# 03_-_OV2640.net
KiCad netlist of a schematic drawn in Altium Designer
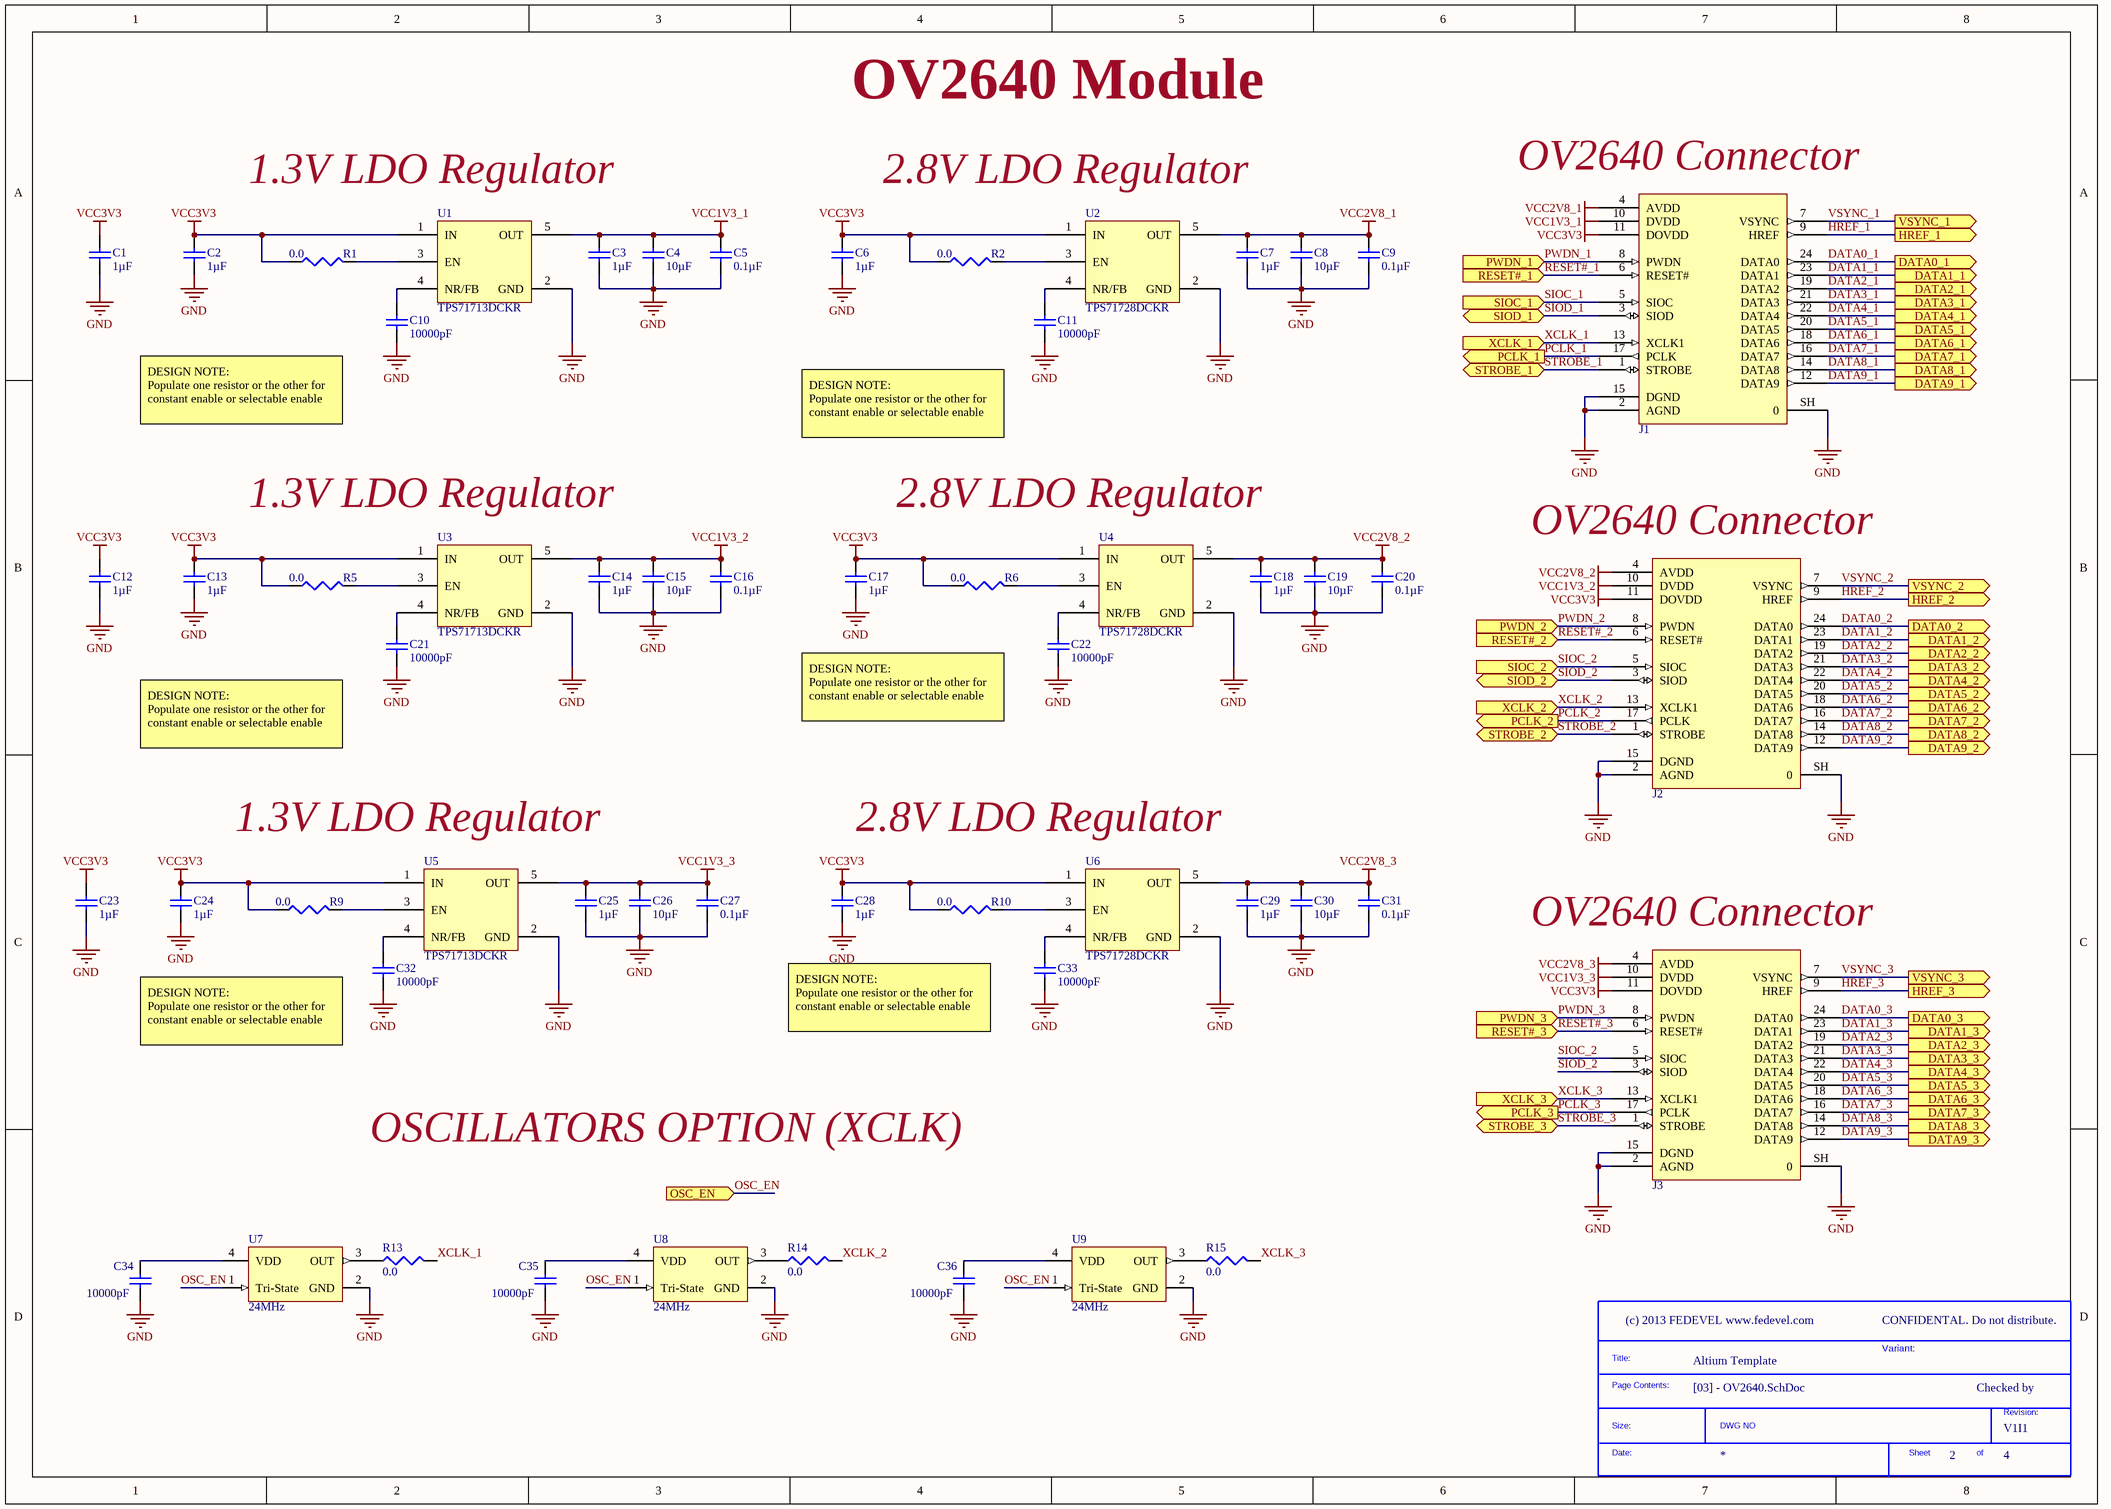
[diagram p0: [03] - OV2640.SchDoc]

(export (version "E")
  (design (tool "Eeschema 10.0.6"))
  (components
    (comp (ref "C1")
      (value "GRM188R71C105KA12D")
      (footprint "CAP-0603")
      (description "CAP CER 1UF 16V X7R 0603")
      (fields
        (field (name "MANUFACTURER") "Murata Electronics North America")
        (field (name "TOLERANCE") "±10%")
        (field (name "CAPACITANCE") "1µF")
      )
      (libsource (lib "camera_module") (part "GRM188R71C105KA12D"))
    )
    (comp (ref "C2")
      (value "GRM188R71C105KA12D")
      (footprint "CAP-0603")
      (description "CAP CER 1UF 16V X7R 0603")
      (fields
        (field (name "MANUFACTURER") "Murata Electronics North America")
        (field (name "TOLERANCE") "±10%")
        (field (name "CAPACITANCE") "1µF")
      )
      (libsource (lib "camera_module") (part "GRM188R71C105KA12D"))
    )
    (comp (ref "C3")
      (value "GRM188R71C105KA12D")
      (footprint "CAP-0603")
      (description "CAP CER 1UF 16V X7R 0603")
      (fields
        (field (name "MANUFACTURER") "Murata Electronics North America")
        (field (name "TOLERANCE") "±10%")
        (field (name "CAPACITANCE") "1µF")
      )
      (libsource (lib "camera_module") (part "GRM188R71C105KA12D"))
    )
    (comp (ref "C4")
      (value "GRM21BR61E106KA73L")
      (footprint "CAP-0805")
      (description "CAP CER 10UF 25V X5R 0805")
      (fields
        (field (name "MANUFACTURER") "Murata Electronics North America")
        (field (name "TOLERANCE") "±10%")
        (field (name "CAPACITANCE") "10µF")
      )
      (libsource (lib "camera_module") (part "GRM21BR61E106KA73L"))
    )
    (comp (ref "C5")
      (value "GRM188R71C104KA01D")
      (footprint "CAP-0603")
      (description "CAP CER 0.1UF 16V X7R 0603")
      (fields
        (field (name "MANUFACTURER") "Murata Electronics North America")
        (field (name "TOLERANCE") "±10%")
        (field (name "CAPACITANCE") "0.1µF")
      )
      (libsource (lib "camera_module") (part "GRM188R71C104KA01D"))
    )
    (comp (ref "C6")
      (value "GRM188R71C105KA12D")
      (footprint "CAP-0603")
      (description "CAP CER 1UF 16V X7R 0603")
      (fields
        (field (name "MANUFACTURER") "Murata Electronics North America")
        (field (name "TOLERANCE") "±10%")
        (field (name "CAPACITANCE") "1µF")
      )
      (libsource (lib "camera_module") (part "GRM188R71C105KA12D"))
    )
    (comp (ref "C7")
      (value "GRM188R71C105KA12D")
      (footprint "CAP-0603")
      (description "CAP CER 1UF 16V X7R 0603")
      (fields
        (field (name "MANUFACTURER") "Murata Electronics North America")
        (field (name "TOLERANCE") "±10%")
        (field (name "CAPACITANCE") "1µF")
      )
      (libsource (lib "camera_module") (part "GRM188R71C105KA12D"))
    )
    (comp (ref "C8")
      (value "GRM21BR61E106KA73L")
      (footprint "CAP-0805")
      (description "CAP CER 10UF 25V X5R 0805")
      (fields
        (field (name "MANUFACTURER") "Murata Electronics North America")
        (field (name "TOLERANCE") "±10%")
        (field (name "CAPACITANCE") "10µF")
      )
      (libsource (lib "camera_module") (part "GRM21BR61E106KA73L"))
    )
    (comp (ref "C9")
      (value "GRM188R71C104KA01D")
      (footprint "CAP-0603")
      (description "CAP CER 0.1UF 16V X7R 0603")
      (fields
        (field (name "MANUFACTURER") "Murata Electronics North America")
        (field (name "TOLERANCE") "±10%")
        (field (name "CAPACITANCE") "0.1µF")
      )
      (libsource (lib "camera_module") (part "GRM188R71C104KA01D"))
    )
    (comp (ref "C10")
      (value "GRM188R71E103KA01D")
      (footprint "CAP-0603")
      (description "CAP CER 10000PF 25V X7R 0603")
      (fields
        (field (name "MANUFACTURER") "Murata Electronics North America")
        (field (name "TOLERANCE") "±10%")
        (field (name "CAPACITANCE") "10000pF")
      )
      (libsource (lib "camera_module") (part "GRM188R71E103KA01D"))
    )
    (comp (ref "C11")
      (value "GRM188R71E103KA01D")
      (footprint "CAP-0603")
      (description "CAP CER 10000PF 25V X7R 0603")
      (fields
        (field (name "MANUFACTURER") "Murata Electronics North America")
        (field (name "TOLERANCE") "±10%")
        (field (name "CAPACITANCE") "10000pF")
      )
      (libsource (lib "camera_module") (part "GRM188R71E103KA01D"))
    )
    (comp (ref "C12")
      (value "GRM188R71C105KA12D")
      (footprint "CAP-0603")
      (description "CAP CER 1UF 16V X7R 0603")
      (fields
        (field (name "MANUFACTURER") "Murata Electronics North America")
        (field (name "TOLERANCE") "±10%")
        (field (name "CAPACITANCE") "1µF")
      )
      (libsource (lib "camera_module") (part "GRM188R71C105KA12D"))
    )
    (comp (ref "C13")
      (value "GRM188R71C105KA12D")
      (footprint "CAP-0603")
      (description "CAP CER 1UF 16V X7R 0603")
      (fields
        (field (name "MANUFACTURER") "Murata Electronics North America")
        (field (name "TOLERANCE") "±10%")
        (field (name "CAPACITANCE") "1µF")
      )
      (libsource (lib "camera_module") (part "GRM188R71C105KA12D"))
    )
    (comp (ref "C14")
      (value "GRM188R71C105KA12D")
      (footprint "CAP-0603")
      (description "CAP CER 1UF 16V X7R 0603")
      (fields
        (field (name "MANUFACTURER") "Murata Electronics North America")
        (field (name "TOLERANCE") "±10%")
        (field (name "CAPACITANCE") "1µF")
      )
      (libsource (lib "camera_module") (part "GRM188R71C105KA12D"))
    )
    (comp (ref "C15")
      (value "GRM21BR61E106KA73L")
      (footprint "CAP-0805")
      (description "CAP CER 10UF 25V X5R 0805")
      (fields
        (field (name "MANUFACTURER") "Murata Electronics North America")
        (field (name "TOLERANCE") "±10%")
        (field (name "CAPACITANCE") "10µF")
      )
      (libsource (lib "camera_module") (part "GRM21BR61E106KA73L"))
    )
    (comp (ref "C16")
      (value "GRM188R71C104KA01D")
      (footprint "CAP-0603")
      (description "CAP CER 0.1UF 16V X7R 0603")
      (fields
        (field (name "MANUFACTURER") "Murata Electronics North America")
        (field (name "TOLERANCE") "±10%")
        (field (name "CAPACITANCE") "0.1µF")
      )
      (libsource (lib "camera_module") (part "GRM188R71C104KA01D"))
    )
    (comp (ref "C17")
      (value "GRM188R71C105KA12D")
      (footprint "CAP-0603")
      (description "CAP CER 1UF 16V X7R 0603")
      (fields
        (field (name "MANUFACTURER") "Murata Electronics North America")
        (field (name "TOLERANCE") "±10%")
        (field (name "CAPACITANCE") "1µF")
      )
      (libsource (lib "camera_module") (part "GRM188R71C105KA12D"))
    )
    (comp (ref "C18")
      (value "GRM188R71C105KA12D")
      (footprint "CAP-0603")
      (description "CAP CER 1UF 16V X7R 0603")
      (fields
        (field (name "MANUFACTURER") "Murata Electronics North America")
        (field (name "TOLERANCE") "±10%")
        (field (name "CAPACITANCE") "1µF")
      )
      (libsource (lib "camera_module") (part "GRM188R71C105KA12D"))
    )
    (comp (ref "C19")
      (value "GRM21BR61E106KA73L")
      (footprint "CAP-0805")
      (description "CAP CER 10UF 25V X5R 0805")
      (fields
        (field (name "MANUFACTURER") "Murata Electronics North America")
        (field (name "TOLERANCE") "±10%")
        (field (name "CAPACITANCE") "10µF")
      )
      (libsource (lib "camera_module") (part "GRM21BR61E106KA73L"))
    )
    (comp (ref "C20")
      (value "GRM188R71C104KA01D")
      (footprint "CAP-0603")
      (description "CAP CER 0.1UF 16V X7R 0603")
      (fields
        (field (name "MANUFACTURER") "Murata Electronics North America")
        (field (name "TOLERANCE") "±10%")
        (field (name "CAPACITANCE") "0.1µF")
      )
      (libsource (lib "camera_module") (part "GRM188R71C104KA01D"))
    )
    (comp (ref "C21")
      (value "GRM188R71E103KA01D")
      (footprint "CAP-0603")
      (description "CAP CER 10000PF 25V X7R 0603")
      (fields
        (field (name "MANUFACTURER") "Murata Electronics North America")
        (field (name "TOLERANCE") "±10%")
        (field (name "CAPACITANCE") "10000pF")
      )
      (libsource (lib "camera_module") (part "GRM188R71E103KA01D"))
    )
    (comp (ref "C22")
      (value "GRM188R71E103KA01D")
      (footprint "CAP-0603")
      (description "CAP CER 10000PF 25V X7R 0603")
      (fields
        (field (name "MANUFACTURER") "Murata Electronics North America")
        (field (name "TOLERANCE") "±10%")
        (field (name "CAPACITANCE") "10000pF")
      )
      (libsource (lib "camera_module") (part "GRM188R71E103KA01D"))
    )
    (comp (ref "C23")
      (value "GRM188R71C105KA12D")
      (footprint "CAP-0603")
      (description "CAP CER 1UF 16V X7R 0603")
      (fields
        (field (name "MANUFACTURER") "Murata Electronics North America")
        (field (name "TOLERANCE") "±10%")
        (field (name "CAPACITANCE") "1µF")
      )
      (libsource (lib "camera_module") (part "GRM188R71C105KA12D"))
    )
    (comp (ref "C24")
      (value "GRM188R71C105KA12D")
      (footprint "CAP-0603")
      (description "CAP CER 1UF 16V X7R 0603")
      (fields
        (field (name "MANUFACTURER") "Murata Electronics North America")
        (field (name "TOLERANCE") "±10%")
        (field (name "CAPACITANCE") "1µF")
      )
      (libsource (lib "camera_module") (part "GRM188R71C105KA12D"))
    )
    (comp (ref "C25")
      (value "GRM188R71C105KA12D")
      (footprint "CAP-0603")
      (description "CAP CER 1UF 16V X7R 0603")
      (fields
        (field (name "MANUFACTURER") "Murata Electronics North America")
        (field (name "TOLERANCE") "±10%")
        (field (name "CAPACITANCE") "1µF")
      )
      (libsource (lib "camera_module") (part "GRM188R71C105KA12D"))
    )
    (comp (ref "C26")
      (value "GRM21BR61E106KA73L")
      (footprint "CAP-0805")
      (description "CAP CER 10UF 25V X5R 0805")
      (fields
        (field (name "MANUFACTURER") "Murata Electronics North America")
        (field (name "TOLERANCE") "±10%")
        (field (name "CAPACITANCE") "10µF")
      )
      (libsource (lib "camera_module") (part "GRM21BR61E106KA73L"))
    )
    (comp (ref "C27")
      (value "GRM188R71C104KA01D")
      (footprint "CAP-0603")
      (description "CAP CER 0.1UF 16V X7R 0603")
      (fields
        (field (name "MANUFACTURER") "Murata Electronics North America")
        (field (name "TOLERANCE") "±10%")
        (field (name "CAPACITANCE") "0.1µF")
      )
      (libsource (lib "camera_module") (part "GRM188R71C104KA01D"))
    )
    (comp (ref "C28")
      (value "GRM188R71C105KA12D")
      (footprint "CAP-0603")
      (description "CAP CER 1UF 16V X7R 0603")
      (fields
        (field (name "MANUFACTURER") "Murata Electronics North America")
        (field (name "TOLERANCE") "±10%")
        (field (name "CAPACITANCE") "1µF")
      )
      (libsource (lib "camera_module") (part "GRM188R71C105KA12D"))
    )
    (comp (ref "C29")
      (value "GRM188R71C105KA12D")
      (footprint "CAP-0603")
      (description "CAP CER 1UF 16V X7R 0603")
      (fields
        (field (name "MANUFACTURER") "Murata Electronics North America")
        (field (name "TOLERANCE") "±10%")
        (field (name "CAPACITANCE") "1µF")
      )
      (libsource (lib "camera_module") (part "GRM188R71C105KA12D"))
    )
    (comp (ref "C30")
      (value "GRM21BR61E106KA73L")
      (footprint "CAP-0805")
      (description "CAP CER 10UF 25V X5R 0805")
      (fields
        (field (name "MANUFACTURER") "Murata Electronics North America")
        (field (name "TOLERANCE") "±10%")
        (field (name "CAPACITANCE") "10µF")
      )
      (libsource (lib "camera_module") (part "GRM21BR61E106KA73L"))
    )
    (comp (ref "C31")
      (value "GRM188R71C104KA01D")
      (footprint "CAP-0603")
      (description "CAP CER 0.1UF 16V X7R 0603")
      (fields
        (field (name "MANUFACTURER") "Murata Electronics North America")
        (field (name "TOLERANCE") "±10%")
        (field (name "CAPACITANCE") "0.1µF")
      )
      (libsource (lib "camera_module") (part "GRM188R71C104KA01D"))
    )
    (comp (ref "C32")
      (value "GRM188R71E103KA01D")
      (footprint "CAP-0603")
      (description "CAP CER 10000PF 25V X7R 0603")
      (fields
        (field (name "MANUFACTURER") "Murata Electronics North America")
        (field (name "TOLERANCE") "±10%")
        (field (name "CAPACITANCE") "10000pF")
      )
      (libsource (lib "camera_module") (part "GRM188R71E103KA01D"))
    )
    (comp (ref "C33")
      (value "GRM188R71E103KA01D")
      (footprint "CAP-0603")
      (description "CAP CER 10000PF 25V X7R 0603")
      (fields
        (field (name "MANUFACTURER") "Murata Electronics North America")
        (field (name "TOLERANCE") "±10%")
        (field (name "CAPACITANCE") "10000pF")
      )
      (libsource (lib "camera_module") (part "GRM188R71E103KA01D"))
    )
    (comp (ref "C34")
      (value "GRM188R71E103KA01D")
      (footprint "CAP-0603")
      (description "CAP CER 10000PF 25V X7R 0603")
      (fields
        (field (name "MANUFACTURER") "Murata Electronics North America")
        (field (name "TOLERANCE") "±10%")
        (field (name "CAPACITANCE") "10000pF")
      )
      (libsource (lib "camera_module") (part "GRM188R71E103KA01D"))
    )
    (comp (ref "C35")
      (value "GRM188R71E103KA01D")
      (footprint "CAP-0603")
      (description "CAP CER 10000PF 25V X7R 0603")
      (fields
        (field (name "MANUFACTURER") "Murata Electronics North America")
        (field (name "TOLERANCE") "±10%")
        (field (name "CAPACITANCE") "10000pF")
      )
      (libsource (lib "camera_module") (part "GRM188R71E103KA01D"))
    )
    (comp (ref "C36")
      (value "GRM188R71E103KA01D")
      (footprint "CAP-0603")
      (description "CAP CER 10000PF 25V X7R 0603")
      (fields
        (field (name "MANUFACTURER") "Murata Electronics North America")
        (field (name "TOLERANCE") "±10%")
        (field (name "CAPACITANCE") "10000pF")
      )
      (libsource (lib "camera_module") (part "GRM188R71E103KA01D"))
    )
    (comp (ref "J1")
      (value "OV2640 FFC")
      (footprint "ov2640FSL")
      (description "CONN FFC BOTTOM 24POS 0.50MM R/A")
      (fields
        (field (name "MANUFACTURER") "Molex, LLC")
        (field (name "MANUFACTURER PART NUMBER") "0524372433")
      )
      (libsource (lib "camera_module") (part "0524372433"))
    )
    (comp (ref "J2")
      (value "OV2640 FFC")
      (footprint "ov2640FSL")
      (description "CONN FFC BOTTOM 24POS 0.50MM R/A")
      (fields
        (field (name "MANUFACTURER") "Molex, LLC")
        (field (name "MANUFACTURER PART NUMBER") "0524372433")
      )
      (libsource (lib "camera_module") (part "0524372433"))
    )
    (comp (ref "J3")
      (value "OV2640 FFC")
      (footprint "ov2640FSL")
      (description "CONN FFC BOTTOM 24POS 0.50MM R/A")
      (fields
        (field (name "MANUFACTURER") "Molex, LLC")
        (field (name "MANUFACTURER PART NUMBER") "0524372433")
      )
      (libsource (lib "camera_module") (part "0524372433"))
    )
    (comp (ref "R1")
      (value "ERJ-3GEY0R00V")
      (footprint "R0603")
      (description "RES SMD 0.0OHM JUMPER 1/10W 0603")
      (fields
        (field (name "MANUFACTURER") "Panasonic Electronic Components")
        (field (name "TOLERANCE") "Jumper")
        (field (name "RESISTANCE (OHMS)") "0.0")
      )
      (libsource (lib "camera_module") (part "ERJ-3GEY0R00V"))
    )
    (comp (ref "R2")
      (value "ERJ-3GEY0R00V")
      (footprint "R0603")
      (description "RES SMD 0.0OHM JUMPER 1/10W 0603")
      (fields
        (field (name "MANUFACTURER") "Panasonic Electronic Components")
        (field (name "TOLERANCE") "Jumper")
        (field (name "RESISTANCE (OHMS)") "0.0")
      )
      (libsource (lib "camera_module") (part "ERJ-3GEY0R00V"))
    )
    (comp (ref "R5")
      (value "ERJ-3GEY0R00V")
      (footprint "R0603")
      (description "RES SMD 0.0OHM JUMPER 1/10W 0603")
      (fields
        (field (name "MANUFACTURER") "Panasonic Electronic Components")
        (field (name "TOLERANCE") "Jumper")
        (field (name "RESISTANCE (OHMS)") "0.0")
      )
      (libsource (lib "camera_module") (part "ERJ-3GEY0R00V"))
    )
    (comp (ref "R6")
      (value "ERJ-3GEY0R00V")
      (footprint "R0603")
      (description "RES SMD 0.0OHM JUMPER 1/10W 0603")
      (fields
        (field (name "MANUFACTURER") "Panasonic Electronic Components")
        (field (name "TOLERANCE") "Jumper")
        (field (name "RESISTANCE (OHMS)") "0.0")
      )
      (libsource (lib "camera_module") (part "ERJ-3GEY0R00V"))
    )
    (comp (ref "R9")
      (value "ERJ-3GEY0R00V")
      (footprint "R0603")
      (description "RES SMD 0.0OHM JUMPER 1/10W 0603")
      (fields
        (field (name "MANUFACTURER") "Panasonic Electronic Components")
        (field (name "TOLERANCE") "Jumper")
        (field (name "RESISTANCE (OHMS)") "0.0")
      )
      (libsource (lib "camera_module") (part "ERJ-3GEY0R00V"))
    )
    (comp (ref "R10")
      (value "ERJ-3GEY0R00V")
      (footprint "R0603")
      (description "RES SMD 0.0OHM JUMPER 1/10W 0603")
      (fields
        (field (name "MANUFACTURER") "Panasonic Electronic Components")
        (field (name "TOLERANCE") "Jumper")
        (field (name "RESISTANCE (OHMS)") "0.0")
      )
      (libsource (lib "camera_module") (part "ERJ-3GEY0R00V"))
    )
    (comp (ref "R13")
      (value "ERJ-3GEY0R00V")
      (footprint "R0603")
      (description "RES SMD 0.0OHM JUMPER 1/10W 0603")
      (fields
        (field (name "MANUFACTURER") "Panasonic Electronic Components")
        (field (name "TOLERANCE") "Jumper")
        (field (name "RESISTANCE (OHMS)") "0.0")
      )
      (libsource (lib "camera_module") (part "ERJ-3GEY0R00V"))
    )
    (comp (ref "R14")
      (value "ERJ-3GEY0R00V")
      (footprint "R0603")
      (description "RES SMD 0.0OHM JUMPER 1/10W 0603")
      (fields
        (field (name "MANUFACTURER") "Panasonic Electronic Components")
        (field (name "TOLERANCE") "Jumper")
        (field (name "RESISTANCE (OHMS)") "0.0")
      )
      (libsource (lib "camera_module") (part "ERJ-3GEY0R00V"))
    )
    (comp (ref "R15")
      (value "ERJ-3GEY0R00V")
      (footprint "R0603")
      (description "RES SMD 0.0OHM JUMPER 1/10W 0603")
      (fields
        (field (name "MANUFACTURER") "Panasonic Electronic Components")
        (field (name "TOLERANCE") "Jumper")
        (field (name "RESISTANCE (OHMS)") "0.0")
      )
      (libsource (lib "camera_module") (part "ERJ-3GEY0R00V"))
    )
    (comp (ref "U1")
      (value "TPS71713DCKR")
      (footprint "SOT65P210X110-5N")
      (description "IC REG LDO 1.3V 0.15A SC70-5")
      (fields (field (name "MANUFACTURER") "Texas Instruments"))
      (libsource (lib "camera_module") (part "TPS71713DCKR"))
    )
    (comp (ref "U2")
      (value "TPS71728DCKR")
      (footprint "SOT65P210X110-5N")
      (description "IC REG LDO 2.8V 0.15A SC70-5")
      (fields (field (name "MANUFACTURER") "Texas Instruments"))
      (libsource (lib "camera_module") (part "TPS71728DCKR"))
    )
    (comp (ref "U3")
      (value "TPS71713DCKR")
      (footprint "SOT65P210X110-5N")
      (description "IC REG LDO 1.3V 0.15A SC70-5")
      (fields (field (name "MANUFACTURER") "Texas Instruments"))
      (libsource (lib "camera_module") (part "TPS71713DCKR"))
    )
    (comp (ref "U4")
      (value "TPS71728DCKR")
      (footprint "SOT65P210X110-5N")
      (description "IC REG LDO 2.8V 0.15A SC70-5")
      (fields (field (name "MANUFACTURER") "Texas Instruments"))
      (libsource (lib "camera_module") (part "TPS71728DCKR"))
    )
    (comp (ref "U5")
      (value "TPS71713DCKR")
      (footprint "SOT65P210X110-5N")
      (description "IC REG LDO 1.3V 0.15A SC70-5")
      (fields (field (name "MANUFACTURER") "Texas Instruments"))
      (libsource (lib "camera_module") (part "TPS71713DCKR"))
    )
    (comp (ref "U6")
      (value "TPS71728DCKR")
      (footprint "SOT65P210X110-5N")
      (description "IC REG LDO 2.8V 0.15A SC70-5")
      (fields (field (name "MANUFACTURER") "Texas Instruments"))
      (libsource (lib "camera_module") (part "TPS71728DCKR"))
    )
    (comp (ref "U7")
      (value "24MHz")
      (footprint "OSC 4-SMD")
      (description "OSC XO 24.000MHZ HCMOS TTL SMD")
      (fields
        (field (name "MANUFACTURER") "Abracon LLC")
        (field (name "MANUFACTURER PART NUMBER") "ASFL1-24.000MHZ-EC-T")
      )
      (libsource (lib "camera_module") (part "ASFL1-24.000MHZ-EC-T"))
    )
    (comp (ref "U8")
      (value "24MHz")
      (footprint "OSC 4-SMD")
      (description "OSC XO 24.000MHZ HCMOS TTL SMD")
      (fields
        (field (name "MANUFACTURER") "Abracon LLC")
        (field (name "MANUFACTURER PART NUMBER") "ASFL1-24.000MHZ-EC-T")
      )
      (libsource (lib "camera_module") (part "ASFL1-24.000MHZ-EC-T"))
    )
    (comp (ref "U9")
      (value "24MHz")
      (footprint "OSC 4-SMD")
      (description "OSC XO 24.000MHZ HCMOS TTL SMD")
      (fields
        (field (name "MANUFACTURER") "Abracon LLC")
        (field (name "MANUFACTURER PART NUMBER") "ASFL1-24.000MHZ-EC-T")
      )
      (libsource (lib "camera_module") (part "ASFL1-24.000MHZ-EC-T"))
    )
  )
  (nets
    (net (code "1") (name "/DATA0_1") (class "Default")
      (node (ref "J1") (pin "24") (pinfunction "DATA0_24") (pintype "output"))
    )
    (net (code "2") (name "/DATA0_2") (class "Default")
      (node (ref "J2") (pin "24") (pinfunction "DATA0_24") (pintype "output"))
    )
    (net (code "3") (name "/DATA0_3") (class "Default")
      (node (ref "J3") (pin "24") (pinfunction "DATA0_24") (pintype "output"))
    )
    (net (code "4") (name "/DATA1_1") (class "Default")
      (node (ref "J1") (pin "23") (pinfunction "DATA1_23") (pintype "output"))
    )
    (net (code "5") (name "/DATA1_2") (class "Default")
      (node (ref "J2") (pin "23") (pinfunction "DATA1_23") (pintype "output"))
    )
    (net (code "6") (name "/DATA1_3") (class "Default")
      (node (ref "J3") (pin "23") (pinfunction "DATA1_23") (pintype "output"))
    )
    (net (code "7") (name "/DATA2_1") (class "Default")
      (node (ref "J1") (pin "19") (pinfunction "DATA2_19") (pintype "output"))
    )
    (net (code "8") (name "/DATA2_2") (class "Default")
      (node (ref "J2") (pin "19") (pinfunction "DATA2_19") (pintype "output"))
    )
    (net (code "9") (name "/DATA2_3") (class "Default")
      (node (ref "J3") (pin "19") (pinfunction "DATA2_19") (pintype "output"))
    )
    (net (code "10") (name "/DATA3_1") (class "Default")
      (node (ref "J1") (pin "21") (pinfunction "DATA3_21") (pintype "output"))
    )
    (net (code "11") (name "/DATA3_2") (class "Default")
      (node (ref "J2") (pin "21") (pinfunction "DATA3_21") (pintype "output"))
    )
    (net (code "12") (name "/DATA3_3") (class "Default")
      (node (ref "J3") (pin "21") (pinfunction "DATA3_21") (pintype "output"))
    )
    (net (code "13") (name "/DATA4_1") (class "Default")
      (node (ref "J1") (pin "22") (pinfunction "DATA4_22") (pintype "output"))
    )
    (net (code "14") (name "/DATA4_2") (class "Default")
      (node (ref "J2") (pin "22") (pinfunction "DATA4_22") (pintype "output"))
    )
    (net (code "15") (name "/DATA4_3") (class "Default")
      (node (ref "J3") (pin "22") (pinfunction "DATA4_22") (pintype "output"))
    )
    (net (code "16") (name "/DATA5_1") (class "Default")
      (node (ref "J1") (pin "20") (pinfunction "DATA5_20") (pintype "output"))
    )
    (net (code "17") (name "/DATA5_2") (class "Default")
      (node (ref "J2") (pin "20") (pinfunction "DATA5_20") (pintype "output"))
    )
    (net (code "18") (name "/DATA5_3") (class "Default")
      (node (ref "J3") (pin "20") (pinfunction "DATA5_20") (pintype "output"))
    )
    (net (code "19") (name "/DATA6_1") (class "Default")
      (node (ref "J1") (pin "18") (pinfunction "DATA6_18") (pintype "output"))
    )
    (net (code "20") (name "/DATA6_2") (class "Default")
      (node (ref "J2") (pin "18") (pinfunction "DATA6_18") (pintype "output"))
    )
    (net (code "21") (name "/DATA6_3") (class "Default")
      (node (ref "J3") (pin "18") (pinfunction "DATA6_18") (pintype "output"))
    )
    (net (code "22") (name "/DATA7_1") (class "Default")
      (node (ref "J1") (pin "16") (pinfunction "DATA7_16") (pintype "output"))
    )
    (net (code "23") (name "/DATA7_2") (class "Default")
      (node (ref "J2") (pin "16") (pinfunction "DATA7_16") (pintype "output"))
    )
    (net (code "24") (name "/DATA7_3") (class "Default")
      (node (ref "J3") (pin "16") (pinfunction "DATA7_16") (pintype "output"))
    )
    (net (code "25") (name "/DATA8_1") (class "Default")
      (node (ref "J1") (pin "14") (pinfunction "DATA8_14") (pintype "output"))
    )
    (net (code "26") (name "/DATA8_2") (class "Default")
      (node (ref "J2") (pin "14") (pinfunction "DATA8_14") (pintype "output"))
    )
    (net (code "27") (name "/DATA8_3") (class "Default")
      (node (ref "J3") (pin "14") (pinfunction "DATA8_14") (pintype "output"))
    )
    (net (code "28") (name "/DATA9_1") (class "Default")
      (node (ref "J1") (pin "12") (pinfunction "DATA9_12") (pintype "output"))
    )
    (net (code "29") (name "/DATA9_2") (class "Default")
      (node (ref "J2") (pin "12") (pinfunction "DATA9_12") (pintype "output"))
    )
    (net (code "30") (name "/DATA9_3") (class "Default")
      (node (ref "J3") (pin "12") (pinfunction "DATA9_12") (pintype "output"))
    )
    (net (code "31") (name "/HREF_1") (class "Default")
      (node (ref "J1") (pin "9") (pinfunction "HREF_9") (pintype "output"))
    )
    (net (code "32") (name "/HREF_2") (class "Default")
      (node (ref "J2") (pin "9") (pinfunction "HREF_9") (pintype "output"))
    )
    (net (code "33") (name "/HREF_3") (class "Default")
      (node (ref "J3") (pin "9") (pinfunction "HREF_9") (pintype "output"))
    )
    (net (code "34") (name "/OSC_EN") (class "Default")
      (node (ref "U7") (pin "1") (pinfunction "Tri-State_1") (pintype "input"))
      (node (ref "U8") (pin "1") (pinfunction "Tri-State_1") (pintype "input"))
      (node (ref "U9") (pin "1") (pinfunction "Tri-State_1") (pintype "input"))
    )
    (net (code "35") (name "/PCLK_1") (class "Default")
      (node (ref "J1") (pin "17") (pinfunction "PCLK_17") (pintype "output"))
    )
    (net (code "36") (name "/PCLK_2") (class "Default")
      (node (ref "J2") (pin "17") (pinfunction "PCLK_17") (pintype "output"))
    )
    (net (code "37") (name "/PCLK_3") (class "Default")
      (node (ref "J3") (pin "17") (pinfunction "PCLK_17") (pintype "output"))
    )
    (net (code "38") (name "/PWDN_1") (class "Default")
      (node (ref "J1") (pin "8") (pinfunction "PWDN_8") (pintype "input"))
    )
    (net (code "39") (name "/PWDN_2") (class "Default")
      (node (ref "J2") (pin "8") (pinfunction "PWDN_8") (pintype "input"))
    )
    (net (code "40") (name "/PWDN_3") (class "Default")
      (node (ref "J3") (pin "8") (pinfunction "PWDN_8") (pintype "input"))
    )
    (net (code "41") (name "/RESET#_1") (class "Default")
      (node (ref "J1") (pin "6") (pinfunction "RESET#_6") (pintype "input"))
    )
    (net (code "42") (name "/RESET#_2") (class "Default")
      (node (ref "J2") (pin "6") (pinfunction "RESET#_6") (pintype "input"))
    )
    (net (code "43") (name "/RESET#_3") (class "Default")
      (node (ref "J3") (pin "6") (pinfunction "RESET#_6") (pintype "input"))
    )
    (net (code "44") (name "/SIOC_1") (class "Default")
      (node (ref "J1") (pin "5") (pinfunction "SIOC_5") (pintype "input"))
    )
    (net (code "45") (name "/SIOC_2") (class "Default")
      (node (ref "J2") (pin "5") (pinfunction "SIOC_5") (pintype "input"))
      (node (ref "J3") (pin "5") (pinfunction "SIOC_5") (pintype "input"))
    )
    (net (code "46") (name "/SIOD_1") (class "Default")
      (node (ref "J1") (pin "3") (pinfunction "SIOD_3") (pintype "bidirectional"))
    )
    (net (code "47") (name "/SIOD_2") (class "Default")
      (node (ref "J2") (pin "3") (pinfunction "SIOD_3") (pintype "bidirectional"))
      (node (ref "J3") (pin "3") (pinfunction "SIOD_3") (pintype "bidirectional"))
    )
    (net (code "48") (name "/STROBE_1") (class "Default")
      (node (ref "J1") (pin "1") (pinfunction "STROBE_1") (pintype "bidirectional"))
    )
    (net (code "49") (name "/STROBE_2") (class "Default")
      (node (ref "J2") (pin "1") (pinfunction "STROBE_1") (pintype "bidirectional"))
    )
    (net (code "50") (name "/STROBE_3") (class "Default")
      (node (ref "J3") (pin "1") (pinfunction "STROBE_1") (pintype "bidirectional"))
    )
    (net (code "51") (name "/VSYNC_1") (class "Default")
      (node (ref "J1") (pin "7") (pinfunction "VSYNC_7") (pintype "output"))
    )
    (net (code "52") (name "/VSYNC_2") (class "Default")
      (node (ref "J2") (pin "7") (pinfunction "VSYNC_7") (pintype "output"))
    )
    (net (code "53") (name "/VSYNC_3") (class "Default")
      (node (ref "J3") (pin "7") (pinfunction "VSYNC_7") (pintype "output"))
    )
    (net (code "54") (name "/XCLK_1") (class "Default")
      (node (ref "J1") (pin "13") (pinfunction "XCLK1_13") (pintype "input"))
      (node (ref "R13") (pin "2") (pinfunction "2_2") (pintype "passive"))
    )
    (net (code "55") (name "/XCLK_2") (class "Default")
      (node (ref "J2") (pin "13") (pinfunction "XCLK1_13") (pintype "input"))
      (node (ref "R14") (pin "2") (pinfunction "2_2") (pintype "passive"))
    )
    (net (code "56") (name "/XCLK_3") (class "Default")
      (node (ref "J3") (pin "13") (pinfunction "XCLK1_13") (pintype "input"))
      (node (ref "R15") (pin "2") (pinfunction "2_2") (pintype "passive"))
    )
    (net (code "57") (name "GND") (class "Default")
      (node (ref "C1") (pin "2") (pinfunction "2_2") (pintype "passive"))
      (node (ref "C10") (pin "2") (pinfunction "2_2") (pintype "passive"))
      (node (ref "C11") (pin "2") (pinfunction "2_2") (pintype "passive"))
      (node (ref "C12") (pin "2") (pinfunction "2_2") (pintype "passive"))
      (node (ref "C13") (pin "2") (pinfunction "2_2") (pintype "passive"))
      (node (ref "C14") (pin "2") (pinfunction "2_2") (pintype "passive"))
      (node (ref "C15") (pin "2") (pinfunction "2_2") (pintype "passive"))
      (node (ref "C16") (pin "2") (pinfunction "2_2") (pintype "passive"))
      (node (ref "C17") (pin "2") (pinfunction "2_2") (pintype "passive"))
      (node (ref "C18") (pin "2") (pinfunction "2_2") (pintype "passive"))
      (node (ref "C19") (pin "2") (pinfunction "2_2") (pintype "passive"))
      (node (ref "C2") (pin "2") (pinfunction "2_2") (pintype "passive"))
      (node (ref "C20") (pin "2") (pinfunction "2_2") (pintype "passive"))
      (node (ref "C21") (pin "2") (pinfunction "2_2") (pintype "passive"))
      (node (ref "C22") (pin "2") (pinfunction "2_2") (pintype "passive"))
      (node (ref "C23") (pin "2") (pinfunction "2_2") (pintype "passive"))
      (node (ref "C24") (pin "2") (pinfunction "2_2") (pintype "passive"))
      (node (ref "C25") (pin "2") (pinfunction "2_2") (pintype "passive"))
      (node (ref "C26") (pin "2") (pinfunction "2_2") (pintype "passive"))
      (node (ref "C27") (pin "2") (pinfunction "2_2") (pintype "passive"))
      (node (ref "C28") (pin "2") (pinfunction "2_2") (pintype "passive"))
      (node (ref "C29") (pin "2") (pinfunction "2_2") (pintype "passive"))
      (node (ref "C3") (pin "2") (pinfunction "2_2") (pintype "passive"))
      (node (ref "C30") (pin "2") (pinfunction "2_2") (pintype "passive"))
      (node (ref "C31") (pin "2") (pinfunction "2_2") (pintype "passive"))
      (node (ref "C32") (pin "2") (pinfunction "2_2") (pintype "passive"))
      (node (ref "C33") (pin "2") (pinfunction "2_2") (pintype "passive"))
      (node (ref "C34") (pin "2") (pinfunction "2_2") (pintype "passive"))
      (node (ref "C35") (pin "2") (pinfunction "2_2") (pintype "passive"))
      (node (ref "C36") (pin "2") (pinfunction "2_2") (pintype "passive"))
      (node (ref "C4") (pin "2") (pinfunction "2_2") (pintype "passive"))
      (node (ref "C5") (pin "2") (pinfunction "2_2") (pintype "passive"))
      (node (ref "C6") (pin "2") (pinfunction "2_2") (pintype "passive"))
      (node (ref "C7") (pin "2") (pinfunction "2_2") (pintype "passive"))
      (node (ref "C8") (pin "2") (pinfunction "2_2") (pintype "passive"))
      (node (ref "C9") (pin "2") (pinfunction "2_2") (pintype "passive"))
      (node (ref "J1") (pin "15") (pinfunction "DGND_15") (pintype "power_in"))
      (node (ref "J1") (pin "2") (pinfunction "AGND_2") (pintype "power_in"))
      (node (ref "J1") (pin "SH") (pinfunction "0_SH") (pintype "power_in"))
      (node (ref "J2") (pin "15") (pinfunction "DGND_15") (pintype "power_in"))
      (node (ref "J2") (pin "2") (pinfunction "AGND_2") (pintype "power_in"))
      (node (ref "J2") (pin "SH") (pinfunction "0_SH") (pintype "power_in"))
      (node (ref "J3") (pin "15") (pinfunction "DGND_15") (pintype "power_in"))
      (node (ref "J3") (pin "2") (pinfunction "AGND_2") (pintype "power_in"))
      (node (ref "J3") (pin "SH") (pinfunction "0_SH") (pintype "power_in"))
      (node (ref "U1") (pin "2") (pinfunction "GND_2") (pintype "passive"))
      (node (ref "U2") (pin "2") (pinfunction "GND_2") (pintype "passive"))
      (node (ref "U3") (pin "2") (pinfunction "GND_2") (pintype "passive"))
      (node (ref "U4") (pin "2") (pinfunction "GND_2") (pintype "passive"))
      (node (ref "U5") (pin "2") (pinfunction "GND_2") (pintype "passive"))
      (node (ref "U6") (pin "2") (pinfunction "GND_2") (pintype "passive"))
      (node (ref "U7") (pin "2") (pinfunction "GND_2") (pintype "power_in"))
      (node (ref "U8") (pin "2") (pinfunction "GND_2") (pintype "power_in"))
      (node (ref "U9") (pin "2") (pinfunction "GND_2") (pintype "power_in"))
    )
    (net (code "58") (name "Net-(U1-EN)") (class "Default")
      (node (ref "R1") (pin "2") (pinfunction "2_2") (pintype "passive"))
      (node (ref "U1") (pin "3") (pinfunction "EN_3") (pintype "passive"))
    )
    (net (code "59") (name "Net-(U1-NR{slash}FB)") (class "Default")
      (node (ref "C10") (pin "1") (pinfunction "1_1") (pintype "passive"))
      (node (ref "U1") (pin "4") (pinfunction "NR/FB_4") (pintype "passive"))
    )
    (net (code "60") (name "Net-(U2-EN)") (class "Default")
      (node (ref "R2") (pin "2") (pinfunction "2_2") (pintype "passive"))
      (node (ref "U2") (pin "3") (pinfunction "EN_3") (pintype "passive"))
    )
    (net (code "61") (name "Net-(U2-NR{slash}FB)") (class "Default")
      (node (ref "C11") (pin "1") (pinfunction "1_1") (pintype "passive"))
      (node (ref "U2") (pin "4") (pinfunction "NR/FB_4") (pintype "passive"))
    )
    (net (code "62") (name "Net-(U3-EN)") (class "Default")
      (node (ref "R5") (pin "2") (pinfunction "2_2") (pintype "passive"))
      (node (ref "U3") (pin "3") (pinfunction "EN_3") (pintype "passive"))
    )
    (net (code "63") (name "Net-(U3-NR{slash}FB)") (class "Default")
      (node (ref "C21") (pin "1") (pinfunction "1_1") (pintype "passive"))
      (node (ref "U3") (pin "4") (pinfunction "NR/FB_4") (pintype "passive"))
    )
    (net (code "64") (name "Net-(U4-EN)") (class "Default")
      (node (ref "R6") (pin "2") (pinfunction "2_2") (pintype "passive"))
      (node (ref "U4") (pin "3") (pinfunction "EN_3") (pintype "passive"))
    )
    (net (code "65") (name "Net-(U4-NR{slash}FB)") (class "Default")
      (node (ref "C22") (pin "1") (pinfunction "1_1") (pintype "passive"))
      (node (ref "U4") (pin "4") (pinfunction "NR/FB_4") (pintype "passive"))
    )
    (net (code "66") (name "Net-(U5-EN)") (class "Default")
      (node (ref "R9") (pin "2") (pinfunction "2_2") (pintype "passive"))
      (node (ref "U5") (pin "3") (pinfunction "EN_3") (pintype "passive"))
    )
    (net (code "67") (name "Net-(U5-NR{slash}FB)") (class "Default")
      (node (ref "C32") (pin "1") (pinfunction "1_1") (pintype "passive"))
      (node (ref "U5") (pin "4") (pinfunction "NR/FB_4") (pintype "passive"))
    )
    (net (code "68") (name "Net-(U6-EN)") (class "Default")
      (node (ref "R10") (pin "2") (pinfunction "2_2") (pintype "passive"))
      (node (ref "U6") (pin "3") (pinfunction "EN_3") (pintype "passive"))
    )
    (net (code "69") (name "Net-(U6-NR{slash}FB)") (class "Default")
      (node (ref "C33") (pin "1") (pinfunction "1_1") (pintype "passive"))
      (node (ref "U6") (pin "4") (pinfunction "NR/FB_4") (pintype "passive"))
    )
    (net (code "70") (name "Net-(U7-OUT)") (class "Default")
      (node (ref "R13") (pin "1") (pinfunction "1_1") (pintype "passive"))
      (node (ref "U7") (pin "3") (pinfunction "OUT_3") (pintype "output"))
    )
    (net (code "71") (name "Net-(U7-VDD)") (class "Default")
      (node (ref "C34") (pin "1") (pinfunction "1_1") (pintype "passive"))
      (node (ref "U7") (pin "4") (pinfunction "VDD_4") (pintype "power_in"))
    )
    (net (code "72") (name "Net-(U8-OUT)") (class "Default")
      (node (ref "R14") (pin "1") (pinfunction "1_1") (pintype "passive"))
      (node (ref "U8") (pin "3") (pinfunction "OUT_3") (pintype "output"))
    )
    (net (code "73") (name "Net-(U8-VDD)") (class "Default")
      (node (ref "C35") (pin "1") (pinfunction "1_1") (pintype "passive"))
      (node (ref "U8") (pin "4") (pinfunction "VDD_4") (pintype "power_in"))
    )
    (net (code "74") (name "Net-(U9-OUT)") (class "Default")
      (node (ref "R15") (pin "1") (pinfunction "1_1") (pintype "passive"))
      (node (ref "U9") (pin "3") (pinfunction "OUT_3") (pintype "output"))
    )
    (net (code "75") (name "Net-(U9-VDD)") (class "Default")
      (node (ref "C36") (pin "1") (pinfunction "1_1") (pintype "passive"))
      (node (ref "U9") (pin "4") (pinfunction "VDD_4") (pintype "power_in"))
    )
    (net (code "76") (name "VCC1V3_1") (class "Default")
      (node (ref "C3") (pin "1") (pinfunction "1_1") (pintype "passive"))
      (node (ref "C4") (pin "1") (pinfunction "1_1") (pintype "passive"))
      (node (ref "C5") (pin "1") (pinfunction "1_1") (pintype "passive"))
      (node (ref "J1") (pin "10") (pinfunction "DVDD_10") (pintype "power_in"))
      (node (ref "U1") (pin "5") (pinfunction "OUT_5") (pintype "passive"))
    )
    (net (code "77") (name "VCC1V3_2") (class "Default")
      (node (ref "C14") (pin "1") (pinfunction "1_1") (pintype "passive"))
      (node (ref "C15") (pin "1") (pinfunction "1_1") (pintype "passive"))
      (node (ref "C16") (pin "1") (pinfunction "1_1") (pintype "passive"))
      (node (ref "J2") (pin "10") (pinfunction "DVDD_10") (pintype "power_in"))
      (node (ref "U3") (pin "5") (pinfunction "OUT_5") (pintype "passive"))
    )
    (net (code "78") (name "VCC1V3_3") (class "Default")
      (node (ref "C25") (pin "1") (pinfunction "1_1") (pintype "passive"))
      (node (ref "C26") (pin "1") (pinfunction "1_1") (pintype "passive"))
      (node (ref "C27") (pin "1") (pinfunction "1_1") (pintype "passive"))
      (node (ref "J3") (pin "10") (pinfunction "DVDD_10") (pintype "power_in"))
      (node (ref "U5") (pin "5") (pinfunction "OUT_5") (pintype "passive"))
    )
    (net (code "79") (name "VCC2V8_1") (class "Default")
      (node (ref "C7") (pin "1") (pinfunction "1_1") (pintype "passive"))
      (node (ref "C8") (pin "1") (pinfunction "1_1") (pintype "passive"))
      (node (ref "C9") (pin "1") (pinfunction "1_1") (pintype "passive"))
      (node (ref "J1") (pin "4") (pinfunction "AVDD_4") (pintype "power_in"))
      (node (ref "U2") (pin "5") (pinfunction "OUT_5") (pintype "passive"))
    )
    (net (code "80") (name "VCC2V8_2") (class "Default")
      (node (ref "C18") (pin "1") (pinfunction "1_1") (pintype "passive"))
      (node (ref "C19") (pin "1") (pinfunction "1_1") (pintype "passive"))
      (node (ref "C20") (pin "1") (pinfunction "1_1") (pintype "passive"))
      (node (ref "J2") (pin "4") (pinfunction "AVDD_4") (pintype "power_in"))
      (node (ref "U4") (pin "5") (pinfunction "OUT_5") (pintype "passive"))
    )
    (net (code "81") (name "VCC2V8_3") (class "Default")
      (node (ref "C29") (pin "1") (pinfunction "1_1") (pintype "passive"))
      (node (ref "C30") (pin "1") (pinfunction "1_1") (pintype "passive"))
      (node (ref "C31") (pin "1") (pinfunction "1_1") (pintype "passive"))
      (node (ref "J3") (pin "4") (pinfunction "AVDD_4") (pintype "power_in"))
      (node (ref "U6") (pin "5") (pinfunction "OUT_5") (pintype "passive"))
    )
    (net (code "82") (name "VCC3V3") (class "Default")
      (node (ref "C1") (pin "1") (pinfunction "1_1") (pintype "passive"))
      (node (ref "C12") (pin "1") (pinfunction "1_1") (pintype "passive"))
      (node (ref "C13") (pin "1") (pinfunction "1_1") (pintype "passive"))
      (node (ref "C17") (pin "1") (pinfunction "1_1") (pintype "passive"))
      (node (ref "C2") (pin "1") (pinfunction "1_1") (pintype "passive"))
      (node (ref "C23") (pin "1") (pinfunction "1_1") (pintype "passive"))
      (node (ref "C24") (pin "1") (pinfunction "1_1") (pintype "passive"))
      (node (ref "C28") (pin "1") (pinfunction "1_1") (pintype "passive"))
      (node (ref "C6") (pin "1") (pinfunction "1_1") (pintype "passive"))
      (node (ref "J1") (pin "11") (pinfunction "DOVDD_11") (pintype "power_in"))
      (node (ref "J2") (pin "11") (pinfunction "DOVDD_11") (pintype "power_in"))
      (node (ref "J3") (pin "11") (pinfunction "DOVDD_11") (pintype "power_in"))
      (node (ref "R1") (pin "1") (pinfunction "1_1") (pintype "passive"))
      (node (ref "R10") (pin "1") (pinfunction "1_1") (pintype "passive"))
      (node (ref "R2") (pin "1") (pinfunction "1_1") (pintype "passive"))
      (node (ref "R5") (pin "1") (pinfunction "1_1") (pintype "passive"))
      (node (ref "R6") (pin "1") (pinfunction "1_1") (pintype "passive"))
      (node (ref "R9") (pin "1") (pinfunction "1_1") (pintype "passive"))
      (node (ref "U1") (pin "1") (pinfunction "IN_1") (pintype "passive"))
      (node (ref "U2") (pin "1") (pinfunction "IN_1") (pintype "passive"))
      (node (ref "U3") (pin "1") (pinfunction "IN_1") (pintype "passive"))
      (node (ref "U4") (pin "1") (pinfunction "IN_1") (pintype "passive"))
      (node (ref "U5") (pin "1") (pinfunction "IN_1") (pintype "passive"))
      (node (ref "U6") (pin "1") (pinfunction "IN_1") (pintype "passive"))
    )
  )
)
